# EasyEDA_MEMS_FPC_V12.net
KiCad netlist of a schematic drawn in EasyEDA Pro
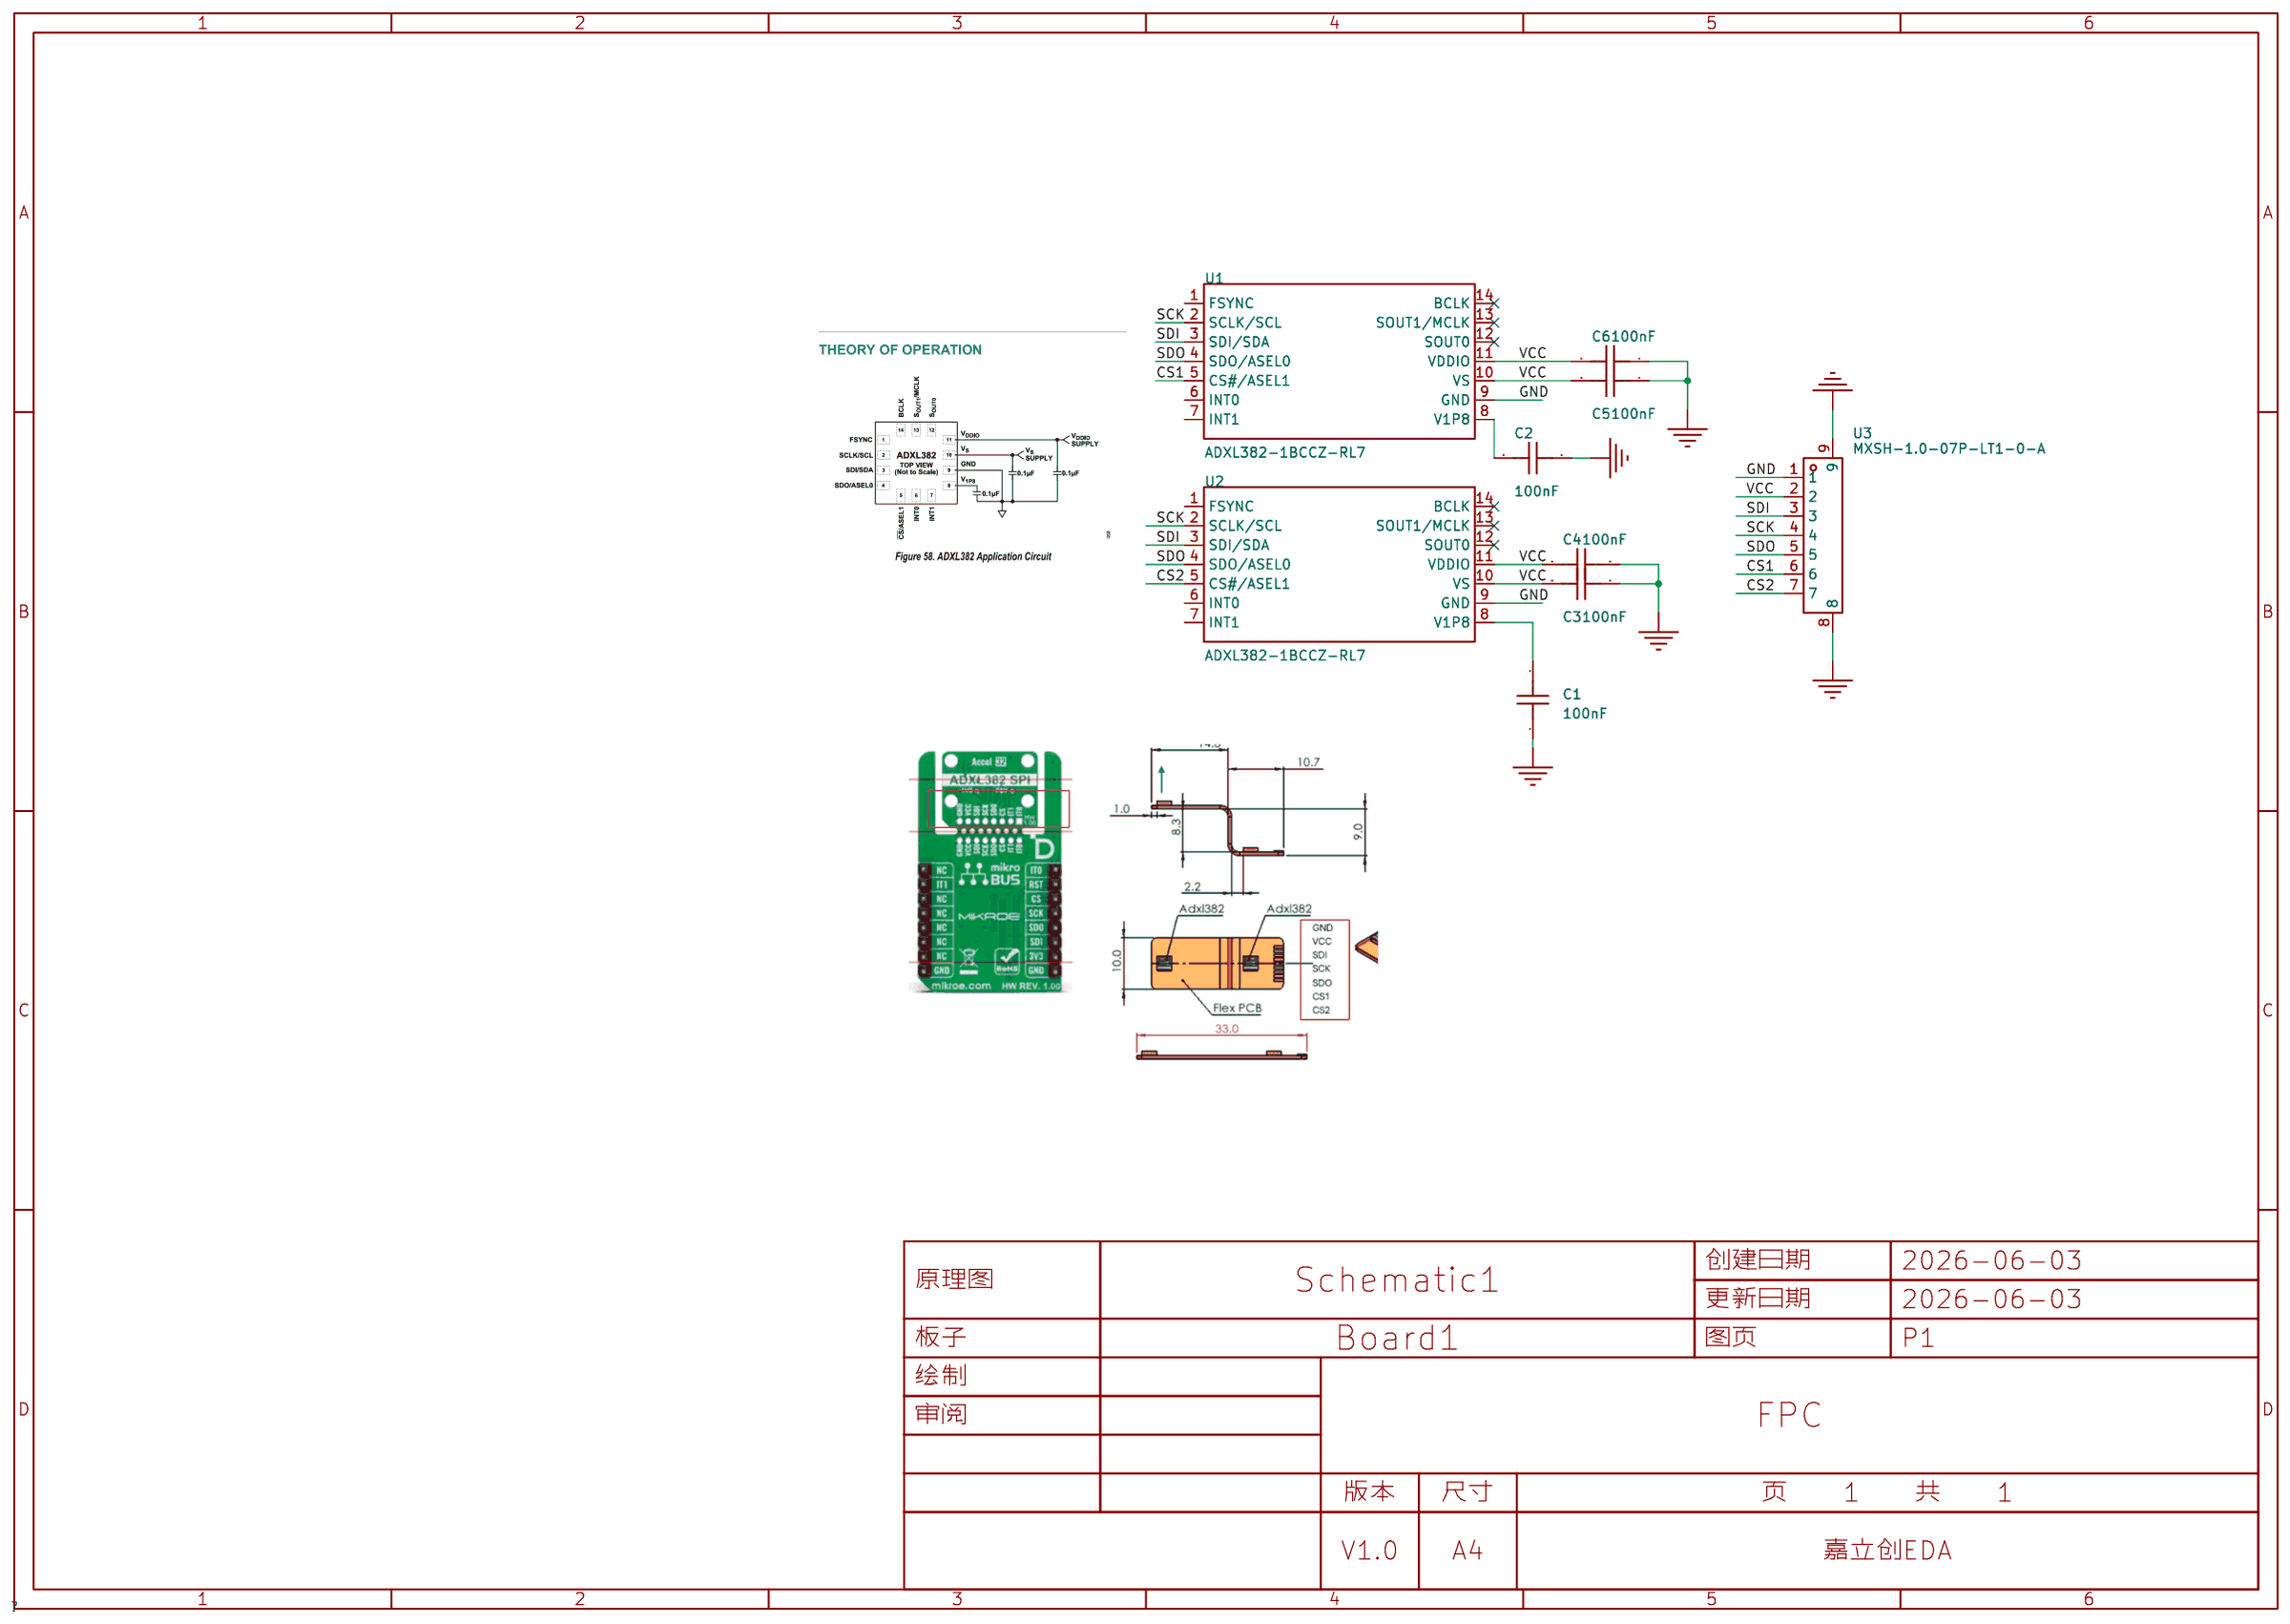
[diagram p0: schematic sheet]

(export (version "E")
  (design (tool "Eeschema 10.0.6"))
  (components
    (comp (ref "C1")
      (value "100nF")
      (footprint "easyedapro:C0402")
      (fields
        (field (name "Manufacturer Part") "CL05B104KO5NNNC")
        (field (name "Manufacturer") "SAMSUNG(三星)")
      )
      (libsource (lib "easyedapro") (part "CL05B104KO5NNNC"))
    )
    (comp (ref "C2")
      (value "100nF")
      (footprint "easyedapro:C0402")
      (fields
        (field (name "Manufacturer Part") "CL05B104KO5NNNC")
        (field (name "Manufacturer") "SAMSUNG(三星)")
      )
      (libsource (lib "easyedapro") (part "CL05B104KO5NNNC"))
    )
    (comp (ref "C3")
      (value "100nF")
      (footprint "easyedapro:C0402")
      (fields
        (field (name "Manufacturer Part") "CL05B104KO5NNNC")
        (field (name "Manufacturer") "SAMSUNG(三星)")
      )
      (libsource (lib "easyedapro") (part "CL05B104KO5NNNC"))
    )
    (comp (ref "C4")
      (value "100nF")
      (footprint "easyedapro:C0402")
      (fields
        (field (name "Manufacturer Part") "CL05B104KO5NNNC")
        (field (name "Manufacturer") "SAMSUNG(三星)")
      )
      (libsource (lib "easyedapro") (part "CL05B104KO5NNNC"))
    )
    (comp (ref "C5")
      (value "100nF")
      (footprint "easyedapro:C0402")
      (fields
        (field (name "Manufacturer Part") "CL05B104KO5NNNC")
        (field (name "Manufacturer") "SAMSUNG(三星)")
      )
      (libsource (lib "easyedapro") (part "CL05B104KO5NNNC"))
    )
    (comp (ref "C6")
      (value "100nF")
      (footprint "easyedapro:C0402")
      (fields
        (field (name "Manufacturer Part") "CL05B104KO5NNNC")
        (field (name "Manufacturer") "SAMSUNG(三星)")
      )
      (libsource (lib "easyedapro") (part "CL05B104KO5NNNC"))
    )
    (comp (ref "U1")
      (value "ADXL382-1BCCZ-RL7")
      (footprint "easyedapro:LGA-14_L2.9-W2.8-P0.50-TL_CC-14-3")
      (fields (field (name "Manufacturer") "ADI(亚德诺)"))
      (libsource (lib "easyedapro") (part "ADXL382-1BCCZ-RL7_C41718413"))
    )
    (comp (ref "U2")
      (value "ADXL382-1BCCZ-RL7")
      (footprint "easyedapro:LGA-14_L2.9-W2.8-P0.50-TL_CC-14-3")
      (fields (field (name "Manufacturer") "ADI(亚德诺)"))
      (libsource (lib "easyedapro") (part "ADXL382-1BCCZ-RL7_C41718413"))
    )
    (comp (ref "U3")
      (value "MXSH-1.0-07P-LT1-0-A")
      (footprint "easyedapro:CONN-SMD_7P-P1.00_MAX_MXSH-1.0-07P-LT1-0-A")
      (fields (field (name "Manufacturer") "MAX(迈旭)"))
      (libsource (lib "easyedapro") (part "MXSH-1.0-07P-LT1-0-A"))
    )
  )
  (nets
    (net (code "1") (name "/CS1") (class "Default")
      (node (ref "U1") (pin "5") (pinfunction "CS#/ASEL1_5") (pintype "unspecified"))
      (node (ref "U3") (pin "6") (pinfunction "6_6") (pintype "unspecified"))
    )
    (net (code "2") (name "/CS2") (class "Default")
      (node (ref "U2") (pin "5") (pinfunction "CS#/ASEL1_5") (pintype "unspecified"))
      (node (ref "U3") (pin "7") (pinfunction "7_7") (pintype "unspecified"))
    )
    (net (code "3") (name "/SCK") (class "Default")
      (node (ref "U1") (pin "2") (pinfunction "SCLK/SCL_2") (pintype "unspecified"))
      (node (ref "U2") (pin "2") (pinfunction "SCLK/SCL_2") (pintype "unspecified"))
      (node (ref "U3") (pin "4") (pinfunction "4_4") (pintype "unspecified"))
    )
    (net (code "4") (name "/SDI") (class "Default")
      (node (ref "U1") (pin "3") (pinfunction "SDI/SDA_3") (pintype "unspecified"))
      (node (ref "U2") (pin "3") (pinfunction "SDI/SDA_3") (pintype "unspecified"))
      (node (ref "U3") (pin "3") (pinfunction "3_3") (pintype "unspecified"))
    )
    (net (code "5") (name "/SDO") (class "Default")
      (node (ref "U1") (pin "4") (pinfunction "SDO/ASEL0_4") (pintype "unspecified"))
      (node (ref "U2") (pin "4") (pinfunction "SDO/ASEL0_4") (pintype "unspecified"))
      (node (ref "U3") (pin "5") (pinfunction "5_5") (pintype "unspecified"))
    )
    (net (code "6") (name "/VCC") (class "Default")
      (node (ref "C3") (pin "2") (pinfunction "2_2") (pintype "unspecified"))
      (node (ref "C4") (pin "2") (pinfunction "2_2") (pintype "unspecified"))
      (node (ref "C5") (pin "2") (pinfunction "2_2") (pintype "unspecified"))
      (node (ref "C6") (pin "2") (pinfunction "2_2") (pintype "unspecified"))
      (node (ref "U1") (pin "10") (pinfunction "VS_10") (pintype "unspecified"))
      (node (ref "U1") (pin "11") (pinfunction "VDDIO_11") (pintype "unspecified"))
      (node (ref "U2") (pin "10") (pinfunction "VS_10") (pintype "unspecified"))
      (node (ref "U2") (pin "11") (pinfunction "VDDIO_11") (pintype "unspecified"))
      (node (ref "U3") (pin "2") (pinfunction "2_2") (pintype "unspecified"))
    )
    (net (code "7") (name "GND") (class "Default")
      (node (ref "C1") (pin "1") (pinfunction "1_1") (pintype "unspecified"))
      (node (ref "C2") (pin "1") (pinfunction "1_1") (pintype "unspecified"))
      (node (ref "C3") (pin "1") (pinfunction "1_1") (pintype "unspecified"))
      (node (ref "C4") (pin "1") (pinfunction "1_1") (pintype "unspecified"))
      (node (ref "C5") (pin "1") (pinfunction "1_1") (pintype "unspecified"))
      (node (ref "C6") (pin "1") (pinfunction "1_1") (pintype "unspecified"))
      (node (ref "U1") (pin "9") (pinfunction "GND_9") (pintype "unspecified"))
      (node (ref "U2") (pin "9") (pinfunction "GND_9") (pintype "unspecified"))
      (node (ref "U3") (pin "1") (pinfunction "1_1") (pintype "unspecified"))
      (node (ref "U3") (pin "8") (pinfunction "8_8") (pintype "unspecified"))
      (node (ref "U3") (pin "9") (pinfunction "9_9") (pintype "unspecified"))
    )
    (net (code "8") (name "Net-(U1-V1P8)") (class "Default")
      (node (ref "C2") (pin "2") (pinfunction "2_2") (pintype "unspecified"))
      (node (ref "U1") (pin "8") (pinfunction "V1P8_8") (pintype "unspecified"))
    )
    (net (code "9") (name "Net-(U2-V1P8)") (class "Default")
      (node (ref "C1") (pin "2") (pinfunction "2_2") (pintype "unspecified"))
      (node (ref "U2") (pin "8") (pinfunction "V1P8_8") (pintype "unspecified"))
    )
    (net (code "10") (name "unconnected-(U1-BCLK-Pad14)") (class "Default")
      (node (ref "U1") (pin "14") (pinfunction "BCLK_14") (pintype "unspecified+no_connect"))
    )
    (net (code "11") (name "unconnected-(U1-FSYNC-Pad1)") (class "Default")
      (node (ref "U1") (pin "1") (pinfunction "FSYNC_1") (pintype "unspecified"))
    )
    (net (code "12") (name "unconnected-(U1-INT0-Pad6)") (class "Default")
      (node (ref "U1") (pin "6") (pinfunction "INT0_6") (pintype "unspecified"))
    )
    (net (code "13") (name "unconnected-(U1-INT1-Pad7)") (class "Default")
      (node (ref "U1") (pin "7") (pinfunction "INT1_7") (pintype "unspecified"))
    )
    (net (code "14") (name "unconnected-(U1-SOUT0-Pad12)") (class "Default")
      (node (ref "U1") (pin "12") (pinfunction "SOUT0_12") (pintype "unspecified+no_connect"))
    )
    (net (code "15") (name "unconnected-(U1-SOUT1{slash}MCLK-Pad13)") (class "Default")
      (node (ref "U1") (pin "13") (pinfunction "SOUT1/MCLK_13") (pintype "unspecified+no_connect"))
    )
    (net (code "16") (name "unconnected-(U2-BCLK-Pad14)") (class "Default")
      (node (ref "U2") (pin "14") (pinfunction "BCLK_14") (pintype "unspecified+no_connect"))
    )
    (net (code "17") (name "unconnected-(U2-FSYNC-Pad1)") (class "Default")
      (node (ref "U2") (pin "1") (pinfunction "FSYNC_1") (pintype "unspecified"))
    )
    (net (code "18") (name "unconnected-(U2-INT0-Pad6)") (class "Default")
      (node (ref "U2") (pin "6") (pinfunction "INT0_6") (pintype "unspecified"))
    )
    (net (code "19") (name "unconnected-(U2-INT1-Pad7)") (class "Default")
      (node (ref "U2") (pin "7") (pinfunction "INT1_7") (pintype "unspecified"))
    )
    (net (code "20") (name "unconnected-(U2-SOUT0-Pad12)") (class "Default")
      (node (ref "U2") (pin "12") (pinfunction "SOUT0_12") (pintype "unspecified+no_connect"))
    )
    (net (code "21") (name "unconnected-(U2-SOUT1{slash}MCLK-Pad13)") (class "Default")
      (node (ref "U2") (pin "13") (pinfunction "SOUT1/MCLK_13") (pintype "unspecified+no_connect"))
    )
  )
)
